# ATmega16_DIP.net
KiCad netlist of a schematic drawn in Altium Designer
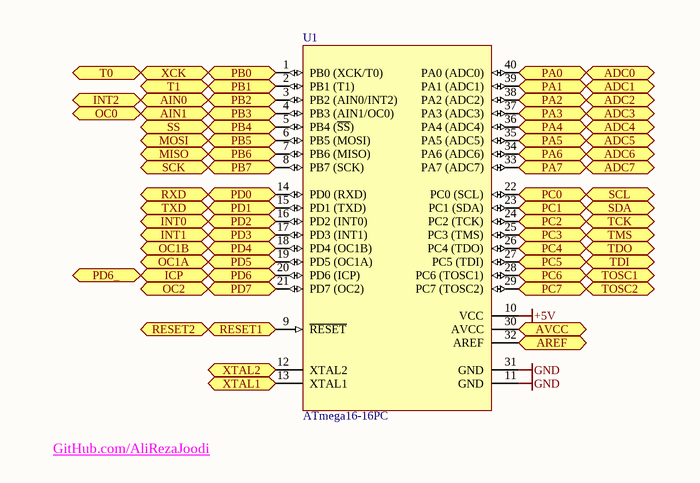
[diagram p0: ATmega16_DIP.SchDoc]

(export (version "E")
  (design (tool "Eeschema 10.0.6"))
  (components
    (comp (ref "U1")
      (value "ATmega16-16PC")
      (footprint "40P6")
      (description "8-Bit AVR Microcontroller with 16K Bytes of In-System Programmable Flash Memory")
      (fields (field (name "PUBLISHER") "Altium Limited"))
      (libsource (lib "Atmel Microcontroller 8-Bit AVR") (part "ATmega16-16PC"))
    )
  )
  (nets
    (net (code "1") (name "+5V") (class "Default")
      (node (ref "U1") (pin "10") (pinfunction "VCC_10") (pintype "power_in"))
    )
    (net (code "32") (name "/AREF") (class "Default")
      (node (ref "U1") (pin "32") (pinfunction "AREF_32") (pintype "passive"))
    )
    (net (code "33") (name "/AVCC") (class "Default")
      (node (ref "U1") (pin "30") (pinfunction "AVCC_30") (pintype "power_in"))
    )
    (net (code "34") (name "/PB0") (class "Default")
      (node (ref "U1") (pin "1") (pinfunction "PB0_(XCK/T0)_1") (pintype "bidirectional"))
    )
    (net (code "35") (name "/PB1") (class "Default")
      (node (ref "U1") (pin "2") (pinfunction "PB1_(T1)_2") (pintype "bidirectional"))
    )
    (net (code "36") (name "/PB2") (class "Default")
      (node (ref "U1") (pin "3") (pinfunction "PB2_(AIN0/INT2)_3") (pintype "bidirectional"))
    )
    (net (code "37") (name "/PB3") (class "Default")
      (node (ref "U1") (pin "4") (pinfunction "PB3_(AIN1/OC0)_4") (pintype "bidirectional"))
    )
    (net (code "38") (name "/PB4") (class "Default")
      (node (ref "U1") (pin "5") (pinfunction "PB4_(~{SS})_5") (pintype "bidirectional"))
    )
    (net (code "39") (name "/PB5") (class "Default")
      (node (ref "U1") (pin "6") (pinfunction "PB5_(MOSI)_6") (pintype "bidirectional"))
    )
    (net (code "48") (name "/PB6") (class "Default")
      (node (ref "U1") (pin "7") (pinfunction "PB6_(MISO)_7") (pintype "bidirectional"))
    )
    (net (code "49") (name "/PB7") (class "Default")
      (node (ref "U1") (pin "8") (pinfunction "PB7_(SCK)_8") (pintype "bidirectional"))
    )
    (net (code "50") (name "/PD0") (class "Default")
      (node (ref "U1") (pin "14") (pinfunction "PD0_(RXD)_14") (pintype "bidirectional"))
    )
    (net (code "51") (name "/PD1") (class "Default")
      (node (ref "U1") (pin "15") (pinfunction "PD1_(TXD)_15") (pintype "bidirectional"))
    )
    (net (code "52") (name "/PD2") (class "Default")
      (node (ref "U1") (pin "16") (pinfunction "PD2_(INT0)_16") (pintype "bidirectional"))
    )
    (net (code "53") (name "/PD3") (class "Default")
      (node (ref "U1") (pin "17") (pinfunction "PD3_(INT1)_17") (pintype "bidirectional"))
    )
    (net (code "54") (name "/PD4") (class "Default")
      (node (ref "U1") (pin "18") (pinfunction "PD4_(OC1B)_18") (pintype "bidirectional"))
    )
    (net (code "56") (name "/PD5") (class "Default")
      (node (ref "U1") (pin "19") (pinfunction "PD5_(OC1A)_19") (pintype "bidirectional"))
    )
    (net (code "57") (name "/PD6") (class "Default")
      (node (ref "U1") (pin "20") (pinfunction "PD6_(ICP)_20") (pintype "bidirectional"))
    )
    (net (code "74") (name "/PD7") (class "Default")
      (node (ref "U1") (pin "21") (pinfunction "PD7_(OC2)_21") (pintype "bidirectional"))
    )
    (net (code "75") (name "/RESET1") (class "Default")
      (node (ref "U1") (pin "9") (pinfunction "~{RESET}_9") (pintype "input"))
    )
    (net (code "76") (name "/XTAL1") (class "Default")
      (node (ref "U1") (pin "13") (pinfunction "XTAL1_13") (pintype "passive"))
    )
    (net (code "77") (name "/XTAL2") (class "Default")
      (node (ref "U1") (pin "12") (pinfunction "XTAL2_12") (pintype "passive"))
    )
    (net (code "78") (name "GND") (class "Default")
      (node (ref "U1") (pin "11") (pinfunction "GND_11") (pintype "power_in"))
      (node (ref "U1") (pin "31") (pinfunction "GND_31") (pintype "power_in"))
    )
    (net (code "79") (name "unconnected-(U1-PA0_(ADC0)-Pad40)") (class "Default")
      (node (ref "U1") (pin "40") (pinfunction "PA0_(ADC0)_40") (pintype "bidirectional"))
    )
    (net (code "80") (name "unconnected-(U1-PA1_(ADC1)-Pad39)") (class "Default")
      (node (ref "U1") (pin "39") (pinfunction "PA1_(ADC1)_39") (pintype "bidirectional"))
    )
    (net (code "81") (name "unconnected-(U1-PA2_(ADC2)-Pad38)") (class "Default")
      (node (ref "U1") (pin "38") (pinfunction "PA2_(ADC2)_38") (pintype "bidirectional"))
    )
    (net (code "82") (name "unconnected-(U1-PA3_(ADC3)-Pad37)") (class "Default")
      (node (ref "U1") (pin "37") (pinfunction "PA3_(ADC3)_37") (pintype "bidirectional"))
    )
    (net (code "83") (name "unconnected-(U1-PA4_(ADC4)-Pad36)") (class "Default")
      (node (ref "U1") (pin "36") (pinfunction "PA4_(ADC4)_36") (pintype "bidirectional"))
    )
    (net (code "84") (name "unconnected-(U1-PA5_(ADC5)-Pad35)") (class "Default")
      (node (ref "U1") (pin "35") (pinfunction "PA5_(ADC5)_35") (pintype "bidirectional"))
    )
    (net (code "85") (name "unconnected-(U1-PA6_(ADC6)-Pad34)") (class "Default")
      (node (ref "U1") (pin "34") (pinfunction "PA6_(ADC6)_34") (pintype "bidirectional"))
    )
    (net (code "86") (name "unconnected-(U1-PA7_(ADC7)-Pad33)") (class "Default")
      (node (ref "U1") (pin "33") (pinfunction "PA7_(ADC7)_33") (pintype "bidirectional"))
    )
    (net (code "87") (name "unconnected-(U1-PC0_(SCL)-Pad22)") (class "Default")
      (node (ref "U1") (pin "22") (pinfunction "PC0_(SCL)_22") (pintype "bidirectional"))
    )
    (net (code "88") (name "unconnected-(U1-PC1_(SDA)-Pad23)") (class "Default")
      (node (ref "U1") (pin "23") (pinfunction "PC1_(SDA)_23") (pintype "bidirectional"))
    )
    (net (code "89") (name "unconnected-(U1-PC2_(TCK)-Pad24)") (class "Default")
      (node (ref "U1") (pin "24") (pinfunction "PC2_(TCK)_24") (pintype "bidirectional"))
    )
    (net (code "90") (name "unconnected-(U1-PC3_(TMS)-Pad25)") (class "Default")
      (node (ref "U1") (pin "25") (pinfunction "PC3_(TMS)_25") (pintype "bidirectional"))
    )
    (net (code "91") (name "unconnected-(U1-PC4_(TDO)-Pad26)") (class "Default")
      (node (ref "U1") (pin "26") (pinfunction "PC4_(TDO)_26") (pintype "bidirectional"))
    )
    (net (code "92") (name "unconnected-(U1-PC5_(TDI)-Pad27)") (class "Default")
      (node (ref "U1") (pin "27") (pinfunction "PC5_(TDI)_27") (pintype "bidirectional"))
    )
    (net (code "93") (name "unconnected-(U1-PC6_(TOSC1)-Pad28)") (class "Default")
      (node (ref "U1") (pin "28") (pinfunction "PC6_(TOSC1)_28") (pintype "bidirectional"))
    )
    (net (code "94") (name "unconnected-(U1-PC7_(TOSC2)-Pad29)") (class "Default")
      (node (ref "U1") (pin "29") (pinfunction "PC7_(TOSC2)_29") (pintype "bidirectional"))
    )
  )
)
